# 07_GSM_EM05.net
KiCad netlist of a schematic drawn in Altium Designer
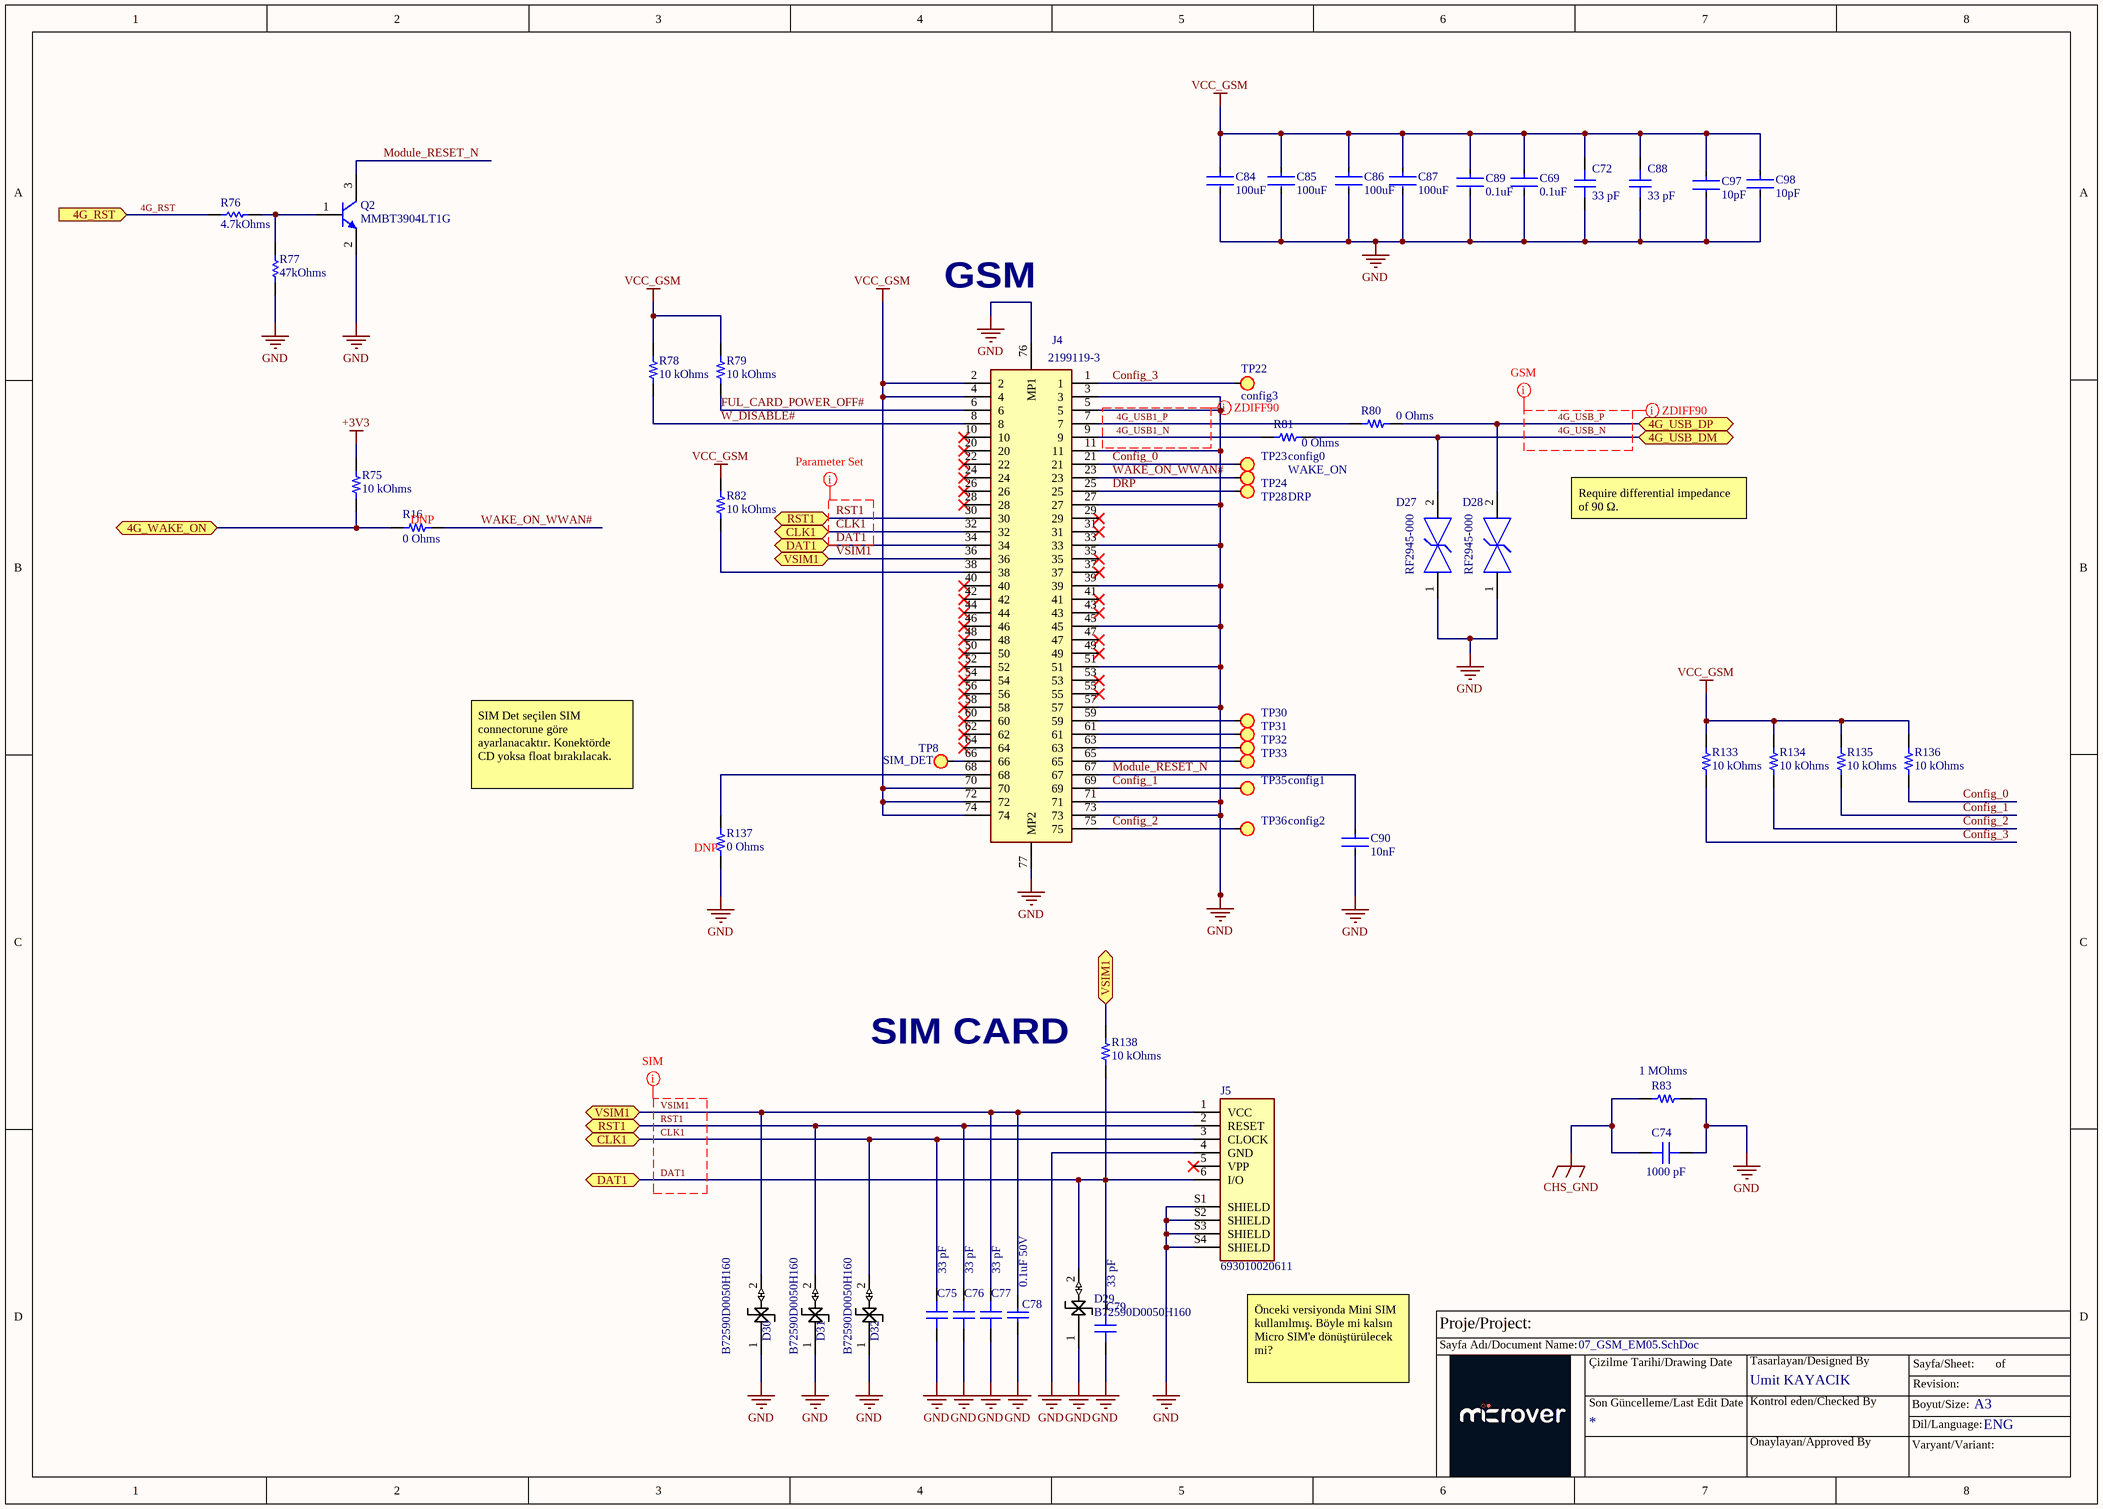
[diagram p0: 07_GSM_EM05.SchDoc]

(export (version "E")
  (design (tool "Eeschema 10.0.6"))
  (components
    (comp (ref "C69")
      (value "0.1uF")
      (footprint "FP-GRM15-MFG")
      (description "CAP CER 0.1UF 16V X7R 0402")
      (fields (field (name "PART NUMBER") "GRM155R71C104KA88D") (field (name "TOLERANCE") "10%"))
      (libsource (lib "Altium Content Vault") (part "236180d848d6139a670b325ea6854c9"))
    )
    (comp (ref "C72")
      (value "33 pF")
      (footprint "CAP0402(1005)X0.5")
      (description "CAP CER 33PF 25V C0G/NP0 0402")
      (fields (field (name "PART NUMBER") "885012005043") (field (name "MANUFACTURER") "Würth Elektronik"))
      (libsource (lib "Celestial Altium Library - altium_library") (part "Capacitor"))
    )
    (comp (ref "C74")
      (value "1000 pF")
      (footprint "CAP 1206_3216 - 0.8MM")
      (description "CAP CER 1000PF 2KV X7R 1206")
      (fields (field (name "PART NUMBER") "202R18W102KV4E"))
      (libsource (lib "Celestial Altium Library - altium_library") (part "Capacitor"))
    )
    (comp (ref "C75")
      (value "33 pF")
      (footprint "CAP 0402_1005")
      (description "CAP CER 33PF 25V C0G/NP0 0402")
      (fields (field (name "PART NUMBER") "885012005043") (field (name "MANUFACTURER") "Würth Elektronik"))
      (libsource (lib "Celestial Altium Library - altium_library") (part "Capacitor"))
    )
    (comp (ref "C76")
      (value "33 pF")
      (footprint "CAP 0402_1005")
      (description "CAP CER 33PF 25V C0G/NP0 0402")
      (fields (field (name "PART NUMBER") "885012005043") (field (name "MANUFACTURER") "Würth Elektronik"))
      (libsource (lib "Celestial Altium Library - altium_library") (part "Capacitor"))
    )
    (comp (ref "C77")
      (value "33 pF")
      (footprint "CAP 0402_1005")
      (description "CAP CER 33PF 25V C0G/NP0 0402")
      (fields (field (name "PART NUMBER") "885012005043") (field (name "MANUFACTURER") "Würth Elektronik"))
      (libsource (lib "Celestial Altium Library - altium_library") (part "Capacitor"))
    )
    (comp (ref "C78")
      (value "0.1uF 50V")
      (footprint "SMC0603")
      (description "0.1 µF ±10% 50V Ceramic Capacitor X7R 0603 (1608 Metric)")
      (fields
        (field (name "MANUFACTURER PART NUMBER") "CL10B104KB8NNNL")
        (field (name "LCSC PART NUMBER") "C1591")
      )
      (libsource (lib "HW_HOLLAND_NCDM_MONITOR_R1") (part "CAP0603_0.1UF_50V"))
    )
    (comp (ref "C79")
      (value "33 pF")
      (footprint "CAP 0402_1005")
      (description "CAP CER 33PF 25V C0G/NP0 0402")
      (fields (field (name "PART NUMBER") "885012005043") (field (name "MANUFACTURER") "Würth Elektronik"))
      (libsource (lib "Celestial Altium Library - altium_library") (part "Capacitor"))
    )
    (comp (ref "C84")
      (value "100uF")
      (footprint "FP-C3216-160-0_3-IPC_C")
      (description "Multilayer Ceramic Capacitors 100uF ±20% 10V X5R SMD 1206")
      (fields (field (name "VOLTAGE") "10V") (field (name "TOLERANCE") "20%"))
      (libsource (lib "Altium Content Vault") (part "02cd4be3c70576c341d710602a673aa"))
    )
    (comp (ref "C85")
      (value "100uF")
      (footprint "FP-C3216-160-0_3-IPC_C")
      (description "Multilayer Ceramic Capacitors 100uF ±20% 10V X5R SMD 1206")
      (fields (field (name "VOLTAGE") "10V") (field (name "TOLERANCE") "20%"))
      (libsource (lib "Altium Content Vault") (part "02cd4be3c70576c341d710602a673aa"))
    )
    (comp (ref "C86")
      (value "100uF")
      (footprint "FP-C3216-160-0_3-IPC_C")
      (description "Multilayer Ceramic Capacitors 100uF ±20% 10V X5R SMD 1206")
      (fields (field (name "VOLTAGE") "10V") (field (name "TOLERANCE") "20%"))
      (libsource (lib "Altium Content Vault") (part "02cd4be3c70576c341d710602a673aa"))
    )
    (comp (ref "C87")
      (value "100uF")
      (footprint "FP-C3216-160-0_3-IPC_C")
      (description "Multilayer Ceramic Capacitors 100uF ±20% 10V X5R SMD 1206")
      (fields (field (name "VOLTAGE") "10V") (field (name "TOLERANCE") "20%"))
      (libsource (lib "Altium Content Vault") (part "02cd4be3c70576c341d710602a673aa"))
    )
    (comp (ref "C88")
      (value "33 pF")
      (footprint "CAP0402(1005)X0.5")
      (description "CAP CER 33PF 25V C0G/NP0 0402")
      (fields (field (name "PART NUMBER") "885012005043") (field (name "MANUFACTURER") "Würth Elektronik"))
      (libsource (lib "Celestial Altium Library - altium_library") (part "Capacitor"))
    )
    (comp (ref "C89")
      (value "0.1uF")
      (footprint "FP-GRM15-MFG")
      (description "CAP CER 0.1UF 16V X7R 0402")
      (fields (field (name "PART NUMBER") "GRM155R71C104KA88D") (field (name "TOLERANCE") "10%"))
      (libsource (lib "Altium Content Vault") (part "236180d848d6139a670b325ea6854c9"))
    )
    (comp (ref "C90")
      (value "10nF")
      (footprint "FP-CL165-IPC_C")
      (description "Cap Ceramic 10nF 50V X7R ±10% SMD 0402 +125°C Paper T/R")
      (fields (field (name "VOLTAGE") "50V") (field (name "TOLERANCE") "10%"))
      (libsource (lib "Altium Content Vault") (part "b4654b650e69147ec39a6b967a45e02"))
    )
    (comp (ref "C97")
      (value "10pF")
      (footprint "FP-CGA2B-MFG")
      (description "Cap Ceramic 10pF 50V C0G 0.5pF Pad SMD 0402 +125°C Automotive T/R")
      (fields (field (name "PART NUMBER") "CGA2B2C0G1H100D050BA"))
      (libsource (lib "Altium Content Vault") (part "b4654b650e69147ec39a6b967a45e02"))
    )
    (comp (ref "C98")
      (value "10pF")
      (footprint "FP-CGA2B-MFG")
      (description "Cap Ceramic 10pF 50V C0G 0.5pF Pad SMD 0402 +125°C Automotive T/R")
      (fields (field (name "PART NUMBER") "CGA2B2C0G1H100D050BA"))
      (libsource (lib "Altium Content Vault") (part "b4654b650e69147ec39a6b967a45e02"))
    )
    (comp (ref "D27")
      (value "RF2945-000")
      (footprint "FP-SESD0402-MFG")
      (description "TVS DIODE 7V 10V 0402")
      (fields
        (field (name "OCTOPART") "https://octopart.com/rf2945-000-littelfuse-56516902")
        (field (name "MANUFACTURER") "Littelfuse")
      )
      (libsource (lib "Altium Content Vault") (part "876f4347bf90aa6f500f43e3cd03972"))
    )
    (comp (ref "D28")
      (value "RF2945-000")
      (footprint "FP-SESD0402-MFG")
      (description "TVS DIODE 7V 10V 0402")
      (fields
        (field (name "OCTOPART") "https://octopart.com/rf2945-000-littelfuse-56516902")
        (field (name "MANUFACTURER") "Littelfuse")
      )
      (libsource (lib "Altium Content Vault") (part "876f4347bf90aa6f500f43e3cd03972"))
    )
    (comp (ref "D29")
      (value "B72590D0050H160")
      (footprint "SOD1005X60N")
      (description "VARISTOR 150V 0402")
      (fields (field (name "MANUFACTURER") "TDK EPCOS"))
      (libsource (lib "HW_HOLLAND_NCDM_MONITOR_R1") (part "B72590D0050H160"))
    )
    (comp (ref "D30")
      (value "B72590D0050H160")
      (footprint "SOD1005X60N")
      (description "VARISTOR 150V 0402")
      (fields (field (name "MANUFACTURER") "TDK EPCOS"))
      (libsource (lib "HW_HOLLAND_NCDM_MONITOR_R1") (part "B72590D0050H160"))
    )
    (comp (ref "D31")
      (value "B72590D0050H160")
      (footprint "SOD1005X60N")
      (description "VARISTOR 150V 0402")
      (fields (field (name "MANUFACTURER") "TDK EPCOS"))
      (libsource (lib "HW_HOLLAND_NCDM_MONITOR_R1") (part "B72590D0050H160"))
    )
    (comp (ref "D32")
      (value "B72590D0050H160")
      (footprint "SOD1005X60N")
      (description "VARISTOR 150V 0402")
      (fields (field (name "MANUFACTURER") "TDK EPCOS"))
      (libsource (lib "HW_HOLLAND_NCDM_MONITOR_R1") (part "B72590D0050H160"))
    )
    (comp (ref "J4")
      (value "2199119-3")
      (footprint "2199119-3")
      (description "Conn Power Card Edge Socket 67 POS 0.5mm Solder RA SMD T/R")
      (fields (field (name "MANUFACTURER") "TE Connectivity"))
      (libsource (lib "HW_HOLLAND_NCDM_MONITOR_R1") (part "2199119-3"))
    )
    (comp (ref "J5")
      (value "693010020611")
      (footprint "WURTH_693010020611")
      (description "WR-CRD Mini SIM Card Connector Header Shielded")
      (fields (field (name "MANUFACTURER") "Wurth Electronics"))
      (libsource (lib "HW_HOLLAND_NCDM_MONITOR_R1") (part "693010020611"))
    )
    (comp (ref "Q2")
      (value "MMBT3904LT1G")
      (footprint "ONSC-SOT-23-3-318-08_V")
      (description "General Purpose Transistor, NPN Silicon, 3-Pin SOT-23, Pb-Free, Tape and Reel")
      (fields (field (name "MANUFACTURER") "On Semiconductor"))
      (libsource (lib "Altium Content Vault") (part "ONSC-NPN-B1E2C3-3"))
    )
    (comp (ref "R16")
      (value "0 Ohms")
      (footprint "RES0402(1005)")
      (description "RES 0 OHM JUMPER 1/8W 0402")
      (fields
        (field (name "PART NUMBER") "HCJ0402ZT0R00")
        (field (name "MANUFACTURER") "Stackpole Electronics Inc")
      )
      (libsource (lib "Celestial Altium Library - altium_library") (part "Resistor"))
    )
    (comp (ref "R75")
      (value "10 kOhms")
      (footprint "RES 0402_1005")
      (description "RES 10K OHM 0.1% 1/10W 0402")
      (fields
        (field (name "PART NUMBER") "RP73PF1E10KBTD")
        (field (name "MANUFACTURER") "TE Connectivity Passive Product")
      )
      (libsource (lib "Celestial Altium Library - altium_library") (part "Resistor"))
    )
    (comp (ref "R76")
      (value "4.7kOhms")
      (footprint "RESC1005X40X25NL05T10")
      (fields (field (name "MANUFACTURER") "Yageo / Phycomp") (field (name "PART NUMBER") "RC0402FR-074K7L"))
      (libsource (lib "Altium Content Vault") (part "RES"))
    )
    (comp (ref "R77")
      (value "47kOhms")
      (footprint "RESC1005X40X25ML05T10")
      (fields (field (name "PART NUMBER") "CRCW040247K0FKEDHP") (field (name "MANUFACTURER") "Vishay Dale"))
      (libsource (lib "Altium Content Vault") (part "RES"))
    )
    (comp (ref "R78")
      (value "10 kOhms")
      (footprint "RES 0402_1005")
      (description "RES 10K OHM 0.1% 1/10W 0402")
      (fields
        (field (name "PART NUMBER") "RP73PF1E10KBTD")
        (field (name "MANUFACTURER") "TE Connectivity Passive Product")
      )
      (libsource (lib "Celestial Altium Library - altium_library") (part "Resistor"))
    )
    (comp (ref "R79")
      (value "10 kOhms")
      (footprint "RES 0402_1005")
      (description "RES 10K OHM 0.1% 1/10W 0402")
      (fields
        (field (name "PART NUMBER") "RP73PF1E10KBTD")
        (field (name "MANUFACTURER") "TE Connectivity Passive Product")
      )
      (libsource (lib "Celestial Altium Library - altium_library") (part "Resistor"))
    )
    (comp (ref "R80")
      (value "0 Ohms")
      (footprint "RES 0402_1005")
      (description "RES 0 OHM JUMPER 1/8W 0402")
      (fields
        (field (name "PART NUMBER") "HCJ0402ZT0R00")
        (field (name "MANUFACTURER") "Stackpole Electronics Inc")
      )
      (libsource (lib "Celestial Altium Library - altium_library") (part "Resistor"))
    )
    (comp (ref "R81")
      (value "0 Ohms")
      (footprint "RES 0402_1005")
      (description "RES 0 OHM JUMPER 1/8W 0402")
      (fields
        (field (name "PART NUMBER") "HCJ0402ZT0R00")
        (field (name "MANUFACTURER") "Stackpole Electronics Inc")
      )
      (libsource (lib "Celestial Altium Library - altium_library") (part "Resistor"))
    )
    (comp (ref "R82")
      (value "10 kOhms")
      (footprint "RES 0402_1005")
      (description "RES 10K OHM 0.1% 1/10W 0402")
      (fields
        (field (name "PART NUMBER") "RP73PF1E10KBTD")
        (field (name "MANUFACTURER") "TE Connectivity Passive Product")
      )
      (libsource (lib "Celestial Altium Library - altium_library") (part "Resistor"))
    )
    (comp (ref "R83")
      (value "1 MOhms")
      (footprint "RES 0402_1005")
      (description "ANTI-SURGE CHIP RESISTORS")
      (fields (field (name "PART NUMBER") "ESR01MZPF1004"))
      (libsource (lib "Celestial Altium Library - altium_library") (part "Resistor"))
    )
    (comp (ref "R133")
      (value "10 kOhms")
      (footprint "RES0402(1005)")
      (description "RES 10K OHM 0.1% 1/10W 0402")
      (fields
        (field (name "PART NUMBER") "RP73PF1E10KBTD")
        (field (name "MANUFACTURER") "TE Connectivity Passive Product")
      )
      (libsource (lib "Celestial Altium Library - altium_library") (part "Resistor"))
    )
    (comp (ref "R134")
      (value "10 kOhms")
      (footprint "RES0402(1005)")
      (description "RES 10K OHM 0.1% 1/10W 0402")
      (fields
        (field (name "PART NUMBER") "RP73PF1E10KBTD")
        (field (name "MANUFACTURER") "TE Connectivity Passive Product")
      )
      (libsource (lib "Celestial Altium Library - altium_library") (part "Resistor"))
    )
    (comp (ref "R135")
      (value "10 kOhms")
      (footprint "RES0402(1005)")
      (description "RES 10K OHM 0.1% 1/10W 0402")
      (fields
        (field (name "PART NUMBER") "RP73PF1E10KBTD")
        (field (name "MANUFACTURER") "TE Connectivity Passive Product")
      )
      (libsource (lib "Celestial Altium Library - altium_library") (part "Resistor"))
    )
    (comp (ref "R136")
      (value "10 kOhms")
      (footprint "RES0402(1005)")
      (description "RES 10K OHM 0.1% 1/10W 0402")
      (fields
        (field (name "PART NUMBER") "RP73PF1E10KBTD")
        (field (name "MANUFACTURER") "TE Connectivity Passive Product")
      )
      (libsource (lib "Celestial Altium Library - altium_library") (part "Resistor"))
    )
    (comp (ref "R137")
      (value "0 Ohms")
      (footprint "RES0402(1005)")
      (description "RES 0 OHM JUMPER 1/8W 0402")
      (fields
        (field (name "PART NUMBER") "HCJ0402ZT0R00")
        (field (name "MANUFACTURER") "Stackpole Electronics Inc")
      )
      (libsource (lib "Celestial Altium Library - altium_library") (part "Resistor"))
    )
    (comp (ref "R138")
      (value "10 kOhms")
      (footprint "RES0402(1005)")
      (description "RES 10K OHM 0.1% 1/10W 0402")
      (fields
        (field (name "PART NUMBER") "RP73PF1E10KBTD")
        (field (name "MANUFACTURER") "TE Connectivity Passive Product")
      )
      (libsource (lib "Celestial Altium Library - altium_library") (part "Resistor"))
    )
    (comp (ref "TP8")
      (value "SIM_DET")
      (footprint "TEST_POINT")
      (libsource (lib "HW_HOLLAND_NCDM_MONITOR_R1") (part "TP_1"))
    )
    (comp (ref "TP22")
      (value "config3")
      (footprint "TEST_POINT")
      (libsource (lib "HW_HOLLAND_NCDM_MONITOR_R1") (part "TP_1"))
    )
    (comp (ref "TP23")
      (value "config0")
      (footprint "TEST_POINT")
      (libsource (lib "HW_HOLLAND_NCDM_MONITOR_R1") (part "TP_1"))
    )
    (comp (ref "TP24")
      (value "WAKE_ON")
      (footprint "TEST_POINT")
      (libsource (lib "HW_HOLLAND_NCDM_MONITOR_R1") (part "TP_1"))
    )
    (comp (ref "TP28")
      (value "DRP")
      (footprint "TEST_POINT")
      (libsource (lib "HW_HOLLAND_NCDM_MONITOR_R1") (part "TP_1"))
    )
    (comp (ref "TP30")
      (value "~")
      (footprint "TEST_POINT")
      (libsource (lib "HW_HOLLAND_NCDM_MONITOR_R1") (part "TP_1"))
    )
    (comp (ref "TP31")
      (value "config0")
      (footprint "TEST_POINT")
      (libsource (lib "HW_HOLLAND_NCDM_MONITOR_R1") (part "TP_1"))
    )
    (comp (ref "TP32")
      (value "~")
      (footprint "TEST_POINT")
      (libsource (lib "HW_HOLLAND_NCDM_MONITOR_R1") (part "TP_1"))
    )
    (comp (ref "TP33")
      (value "~")
      (footprint "TEST_POINT")
      (libsource (lib "HW_HOLLAND_NCDM_MONITOR_R1") (part "TP_1"))
    )
    (comp (ref "TP35")
      (value "config1")
      (footprint "TEST_POINT")
      (libsource (lib "HW_HOLLAND_NCDM_MONITOR_R1") (part "TP_1"))
    )
    (comp (ref "TP36")
      (value "config2")
      (footprint "TEST_POINT")
      (libsource (lib "HW_HOLLAND_NCDM_MONITOR_R1") (part "TP_1"))
    )
  )
  (nets
    (net (code "1") (name "+3V3") (class "Default")
      (node (ref "R75") (pin "2") (pinfunction "2_2") (pintype "passive"))
    )
    (net (code "2") (name "/4G_RST") (class "Default")
      (node (ref "R76") (pin "1") (pinfunction "1_1") (pintype "passive"))
    )
    (net (code "3") (name "/4G_USB1_N") (class "Default")
      (node (ref "J4") (pin "9") (pinfunction "9_9") (pintype "passive"))
      (node (ref "R81") (pin "2") (pinfunction "2_2") (pintype "passive"))
    )
    (net (code "4") (name "/4G_USB1_P") (class "Default")
      (node (ref "J4") (pin "7") (pinfunction "7_7") (pintype "passive"))
      (node (ref "R80") (pin "2") (pinfunction "2_2") (pintype "passive"))
    )
    (net (code "5") (name "/4G_USB_N") (class "Default")
      (node (ref "D27") (pin "2") (pinfunction "2_2") (pintype "passive"))
      (node (ref "R81") (pin "1") (pinfunction "1_1") (pintype "passive"))
    )
    (net (code "6") (name "/4G_USB_P") (class "Default")
      (node (ref "D28") (pin "2") (pinfunction "2_2") (pintype "passive"))
      (node (ref "R80") (pin "1") (pinfunction "1_1") (pintype "passive"))
    )
    (net (code "7") (name "/4G_WAKE_ON") (class "Default")
      (node (ref "R16") (pin "1") (pinfunction "1_1") (pintype "passive"))
      (node (ref "R75") (pin "1") (pinfunction "1_1") (pintype "passive"))
    )
    (net (code "8") (name "/CLK1") (class "Default")
      (node (ref "C75") (pin "2") (pinfunction "2_2") (pintype "passive"))
      (node (ref "D32") (pin "2") (pinfunction "I/OLINE_2") (pintype "bidirectional"))
      (node (ref "J4") (pin "32") (pinfunction "32_32") (pintype "passive"))
      (node (ref "J5") (pin "3") (pinfunction "CLOCK_3") (pintype "passive"))
    )
    (net (code "9") (name "/Config_0") (class "Default")
      (node (ref "J4") (pin "21") (pinfunction "21_21") (pintype "passive"))
      (node (ref "R136") (pin "1") (pinfunction "1_1") (pintype "passive"))
      (node (ref "TP23") (pin "1") (pinfunction "TP_1") (pintype "passive"))
    )
    (net (code "10") (name "/Config_1") (class "Default")
      (node (ref "J4") (pin "69") (pinfunction "69_69") (pintype "passive"))
      (node (ref "R135") (pin "1") (pinfunction "1_1") (pintype "passive"))
      (node (ref "TP35") (pin "1") (pinfunction "TP_1") (pintype "passive"))
    )
    (net (code "11") (name "/Config_2") (class "Default")
      (node (ref "J4") (pin "75") (pinfunction "75_75") (pintype "passive"))
      (node (ref "R134") (pin "1") (pinfunction "1_1") (pintype "passive"))
      (node (ref "TP36") (pin "1") (pinfunction "TP_1") (pintype "passive"))
    )
    (net (code "12") (name "/Config_3") (class "Default")
      (node (ref "J4") (pin "1") (pinfunction "1_1") (pintype "passive"))
      (node (ref "R133") (pin "1") (pinfunction "1_1") (pintype "passive"))
      (node (ref "TP22") (pin "1") (pinfunction "TP_1") (pintype "passive"))
    )
    (net (code "13") (name "/DAT1") (class "Default")
      (node (ref "C79") (pin "2") (pinfunction "2_2") (pintype "passive"))
      (node (ref "D29") (pin "2") (pinfunction "I/OLINE_2") (pintype "bidirectional"))
      (node (ref "J4") (pin "34") (pinfunction "34_34") (pintype "passive"))
      (node (ref "J5") (pin "6") (pinfunction "I/O_6") (pintype "passive"))
      (node (ref "R138") (pin "1") (pinfunction "1_1") (pintype "passive"))
    )
    (net (code "14") (name "/DRP") (class "Default")
      (node (ref "J4") (pin "25") (pinfunction "25_25") (pintype "passive"))
      (node (ref "TP28") (pin "1") (pinfunction "TP_1") (pintype "passive"))
    )
    (net (code "15") (name "/FUL_CARD_POWER_OFF#") (class "Default")
      (node (ref "J4") (pin "6") (pinfunction "6_6") (pintype "passive"))
      (node (ref "R79") (pin "1") (pinfunction "1_1") (pintype "passive"))
    )
    (net (code "16") (name "/Module_RESET_N") (class "Default")
      (node (ref "C90") (pin "1") (pinfunction "1_1") (pintype "passive"))
      (node (ref "J4") (pin "67") (pinfunction "67_67") (pintype "passive"))
      (node (ref "Q2") (pin "3") (pinfunction "C_3") (pintype "passive"))
    )
    (net (code "17") (name "/RST1") (class "Default")
      (node (ref "C76") (pin "2") (pinfunction "2_2") (pintype "passive"))
      (node (ref "D31") (pin "2") (pinfunction "I/OLINE_2") (pintype "bidirectional"))
      (node (ref "J4") (pin "30") (pinfunction "30_30") (pintype "passive"))
      (node (ref "J5") (pin "2") (pinfunction "RESET_2") (pintype "passive"))
    )
    (net (code "18") (name "/VSIM1") (class "Default")
      (node (ref "C77") (pin "2") (pinfunction "2_2") (pintype "passive"))
      (node (ref "C78") (pin "2") (pinfunction "2_2") (pintype "passive"))
      (node (ref "D30") (pin "2") (pinfunction "I/OLINE_2") (pintype "bidirectional"))
      (node (ref "J4") (pin "36") (pinfunction "36_36") (pintype "passive"))
      (node (ref "J5") (pin "1") (pinfunction "VCC_1") (pintype "passive"))
      (node (ref "R138") (pin "2") (pinfunction "2_2") (pintype "passive"))
    )
    (net (code "19") (name "/WAKE_ON_WWAN#") (class "Default")
      (node (ref "J4") (pin "23") (pinfunction "23_23") (pintype "passive"))
      (node (ref "R16") (pin "2") (pinfunction "2_2") (pintype "passive"))
      (node (ref "TP24") (pin "1") (pinfunction "TP_1") (pintype "passive"))
    )
    (net (code "20") (name "/W_DISABLE#") (class "Default")
      (node (ref "J4") (pin "8") (pinfunction "8_8") (pintype "passive"))
      (node (ref "R78") (pin "1") (pinfunction "1_1") (pintype "passive"))
    )
    (net (code "21") (name "CHS_GND") (class "Default")
      (node (ref "C74") (pin "1") (pinfunction "1_1") (pintype "passive"))
      (node (ref "R83") (pin "1") (pinfunction "1_1") (pintype "passive"))
    )
    (net (code "22") (name "GND") (class "Default")
      (node (ref "C69") (pin "1") (pinfunction "1_1") (pintype "passive"))
      (node (ref "C72") (pin "1") (pinfunction "1_1") (pintype "passive"))
      (node (ref "C74") (pin "2") (pinfunction "2_2") (pintype "passive"))
      (node (ref "C75") (pin "1") (pinfunction "1_1") (pintype "passive"))
      (node (ref "C76") (pin "1") (pinfunction "1_1") (pintype "passive"))
      (node (ref "C77") (pin "1") (pinfunction "1_1") (pintype "passive"))
      (node (ref "C78") (pin "1") (pinfunction "1_1") (pintype "passive"))
      (node (ref "C79") (pin "1") (pinfunction "1_1") (pintype "passive"))
      (node (ref "C84") (pin "2") (pinfunction "2_2") (pintype "passive"))
      (node (ref "C85") (pin "2") (pinfunction "2_2") (pintype "passive"))
      (node (ref "C86") (pin "2") (pinfunction "2_2") (pintype "passive"))
      (node (ref "C87") (pin "2") (pinfunction "2_2") (pintype "passive"))
      (node (ref "C88") (pin "1") (pinfunction "1_1") (pintype "passive"))
      (node (ref "C89") (pin "1") (pinfunction "1_1") (pintype "passive"))
      (node (ref "C90") (pin "2") (pinfunction "2_2") (pintype "passive"))
      (node (ref "C97") (pin "2") (pinfunction "2_2") (pintype "passive"))
      (node (ref "C98") (pin "2") (pinfunction "2_2") (pintype "passive"))
      (node (ref "D27") (pin "1") (pinfunction "1_1") (pintype "passive"))
      (node (ref "D28") (pin "1") (pinfunction "1_1") (pintype "passive"))
      (node (ref "D29") (pin "1") (pinfunction "GND_1") (pintype "passive"))
      (node (ref "D30") (pin "1") (pinfunction "GND_1") (pintype "passive"))
      (node (ref "D31") (pin "1") (pinfunction "GND_1") (pintype "passive"))
      (node (ref "D32") (pin "1") (pinfunction "GND_1") (pintype "passive"))
      (node (ref "J4") (pin "11") (pinfunction "11_11") (pintype "passive"))
      (node (ref "J4") (pin "27") (pinfunction "27_27") (pintype "passive"))
      (node (ref "J4") (pin "3") (pinfunction "3_3") (pintype "passive"))
      (node (ref "J4") (pin "33") (pinfunction "33_33") (pintype "passive"))
      (node (ref "J4") (pin "39") (pinfunction "39_39") (pintype "passive"))
      (node (ref "J4") (pin "45") (pinfunction "45_45") (pintype "passive"))
      (node (ref "J4") (pin "5") (pinfunction "5_5") (pintype "passive"))
      (node (ref "J4") (pin "51") (pinfunction "51_51") (pintype "passive"))
      (node (ref "J4") (pin "57") (pinfunction "57_57") (pintype "passive"))
      (node (ref "J4") (pin "71") (pinfunction "71_71") (pintype "passive"))
      (node (ref "J4") (pin "73") (pinfunction "73_73") (pintype "passive"))
      (node (ref "J4") (pin "76") (pinfunction "MP1_76") (pintype "passive"))
      (node (ref "J4") (pin "77") (pinfunction "MP2_77") (pintype "passive"))
      (node (ref "J5") (pin "4") (pinfunction "GND_4") (pintype "passive"))
      (node (ref "J5") (pin "S1") (pinfunction "SHIELD_S1") (pintype "passive"))
      (node (ref "J5") (pin "S2") (pinfunction "SHIELD_S2") (pintype "passive"))
      (node (ref "J5") (pin "S3") (pinfunction "SHIELD_S3") (pintype "passive"))
      (node (ref "J5") (pin "S4") (pinfunction "SHIELD_S4") (pintype "passive"))
      (node (ref "Q2") (pin "2") (pinfunction "E_2") (pintype "passive"))
      (node (ref "R137") (pin "2") (pinfunction "2_2") (pintype "passive"))
      (node (ref "R77") (pin "1") (pinfunction "1_1") (pintype "passive"))
      (node (ref "R83") (pin "2") (pinfunction "2_2") (pintype "passive"))
    )
    (net (code "23") (name "Net-(J4-Pad38)") (class "Default")
      (node (ref "J4") (pin "38") (pinfunction "38_38") (pintype "passive"))
      (node (ref "R82") (pin "1") (pinfunction "1_1") (pintype "passive"))
    )
    (net (code "24") (name "Net-(J4-Pad68)") (class "Default")
      (node (ref "J4") (pin "68") (pinfunction "68_68") (pintype "passive"))
      (node (ref "R137") (pin "1") (pinfunction "1_1") (pintype "passive"))
    )
    (net (code "25") (name "Net-(Q2-B)") (class "Default")
      (node (ref "Q2") (pin "1") (pinfunction "B_1") (pintype "passive"))
      (node (ref "R76") (pin "2") (pinfunction "2_2") (pintype "passive"))
      (node (ref "R77") (pin "2") (pinfunction "2_2") (pintype "passive"))
    )
    (net (code "26") (name "Net-(TP8-TP)") (class "Default")
      (node (ref "J4") (pin "66") (pinfunction "66_66") (pintype "passive"))
      (node (ref "TP8") (pin "1") (pinfunction "TP_1") (pintype "passive"))
    )
    (net (code "27") (name "Net-(TP30-TP)") (class "Default")
      (node (ref "J4") (pin "59") (pinfunction "59_59") (pintype "passive"))
      (node (ref "TP30") (pin "1") (pinfunction "TP_1") (pintype "passive"))
    )
    (net (code "28") (name "Net-(TP31-TP)") (class "Default")
      (node (ref "J4") (pin "61") (pinfunction "61_61") (pintype "passive"))
      (node (ref "TP31") (pin "1") (pinfunction "TP_1") (pintype "passive"))
    )
    (net (code "29") (name "Net-(TP32-TP)") (class "Default")
      (node (ref "J4") (pin "63") (pinfunction "63_63") (pintype "passive"))
      (node (ref "TP32") (pin "1") (pinfunction "TP_1") (pintype "passive"))
    )
    (net (code "30") (name "Net-(TP33-TP)") (class "Default")
      (node (ref "J4") (pin "65") (pinfunction "65_65") (pintype "passive"))
      (node (ref "TP33") (pin "1") (pinfunction "TP_1") (pintype "passive"))
    )
    (net (code "31") (name "VCC_GSM") (class "Default")
      (node (ref "C69") (pin "2") (pinfunction "2_2") (pintype "passive"))
      (node (ref "C72") (pin "2") (pinfunction "2_2") (pintype "passive"))
      (node (ref "C84") (pin "1") (pinfunction "1_1") (pintype "passive"))
      (node (ref "C85") (pin "1") (pinfunction "1_1") (pintype "passive"))
      (node (ref "C86") (pin "1") (pinfunction "1_1") (pintype "passive"))
      (node (ref "C87") (pin "1") (pinfunction "1_1") (pintype "passive"))
      (node (ref "C88") (pin "2") (pinfunction "2_2") (pintype "passive"))
      (node (ref "C89") (pin "2") (pinfunction "2_2") (pintype "passive"))
      (node (ref "C97") (pin "1") (pinfunction "1_1") (pintype "passive"))
      (node (ref "C98") (pin "1") (pinfunction "1_1") (pintype "passive"))
      (node (ref "J4") (pin "2") (pinfunction "2_2") (pintype "passive"))
      (node (ref "J4") (pin "4") (pinfunction "4_4") (pintype "passive"))
      (node (ref "J4") (pin "70") (pinfunction "70_70") (pintype "passive"))
      (node (ref "J4") (pin "72") (pinfunction "72_72") (pintype "passive"))
      (node (ref "J4") (pin "74") (pinfunction "74_74") (pintype "passive"))
      (node (ref "R133") (pin "2") (pinfunction "2_2") (pintype "passive"))
      (node (ref "R134") (pin "2") (pinfunction "2_2") (pintype "passive"))
      (node (ref "R135") (pin "2") (pinfunction "2_2") (pintype "passive"))
      (node (ref "R136") (pin "2") (pinfunction "2_2") (pintype "passive"))
      (node (ref "R78") (pin "2") (pinfunction "2_2") (pintype "passive"))
      (node (ref "R79") (pin "2") (pinfunction "2_2") (pintype "passive"))
      (node (ref "R82") (pin "2") (pinfunction "2_2") (pintype "passive"))
    )
    (net (code "32") (name "unconnected-(J4-Pad10)") (class "Default")
      (node (ref "J4") (pin "10") (pinfunction "10_10") (pintype "passive+no_connect"))
    )
    (net (code "33") (name "unconnected-(J4-Pad20)") (class "Default")
      (node (ref "J4") (pin "20") (pinfunction "20_20") (pintype "passive+no_connect"))
    )
    (net (code "34") (name "unconnected-(J4-Pad22)") (class "Default")
      (node (ref "J4") (pin "22") (pinfunction "22_22") (pintype "passive+no_connect"))
    )
    (net (code "35") (name "unconnected-(J4-Pad24)") (class "Default")
      (node (ref "J4") (pin "24") (pinfunction "24_24") (pintype "passive+no_connect"))
    )
    (net (code "36") (name "unconnected-(J4-Pad26)") (class "Default")
      (node (ref "J4") (pin "26") (pinfunction "26_26") (pintype "passive+no_connect"))
    )
    (net (code "37") (name "unconnected-(J4-Pad28)") (class "Default")
      (node (ref "J4") (pin "28") (pinfunction "28_28") (pintype "passive+no_connect"))
    )
    (net (code "38") (name "unconnected-(J4-Pad29)") (class "Default")
      (node (ref "J4") (pin "29") (pinfunction "29_29") (pintype "passive+no_connect"))
    )
    (net (code "39") (name "unconnected-(J4-Pad31)") (class "Default")
      (node (ref "J4") (pin "31") (pinfunction "31_31") (pintype "passive+no_connect"))
    )
    (net (code "40") (name "unconnected-(J4-Pad35)") (class "Default")
      (node (ref "J4") (pin "35") (pinfunction "35_35") (pintype "passive+no_connect"))
    )
    (net (code "41") (name "unconnected-(J4-Pad37)") (class "Default")
      (node (ref "J4") (pin "37") (pinfunction "37_37") (pintype "passive+no_connect"))
    )
    (net (code "42") (name "unconnected-(J4-Pad40)") (class "Default")
      (node (ref "J4") (pin "40") (pinfunction "40_40") (pintype "passive+no_connect"))
    )
    (net (code "43") (name "unconnected-(J4-Pad41)") (class "Default")
      (node (ref "J4") (pin "41") (pinfunction "41_41") (pintype "passive+no_connect"))
    )
    (net (code "44") (name "unconnected-(J4-Pad42)") (class "Default")
      (node (ref "J4") (pin "42") (pinfunction "42_42") (pintype "passive+no_connect"))
    )
    (net (code "45") (name "unconnected-(J4-Pad43)") (class "Default")
      (node (ref "J4") (pin "43") (pinfunction "43_43") (pintype "passive+no_connect"))
    )
    (net (code "46") (name "unconnected-(J4-Pad44)") (class "Default")
      (node (ref "J4") (pin "44") (pinfunction "44_44") (pintype "passive+no_connect"))
    )
    (net (code "47") (name "unconnected-(J4-Pad46)") (class "Default")
      (node (ref "J4") (pin "46") (pinfunction "46_46") (pintype "passive+no_connect"))
    )
    (net (code "48") (name "unconnected-(J4-Pad47)") (class "Default")
      (node (ref "J4") (pin "47") (pinfunction "47_47") (pintype "passive+no_connect"))
    )
    (net (code "49") (name "unconnected-(J4-Pad48)") (class "Default")
      (node (ref "J4") (pin "48") (pinfunction "48_48") (pintype "passive+no_connect"))
    )
    (net (code "50") (name "unconnected-(J4-Pad49)") (class "Default")
      (node (ref "J4") (pin "49") (pinfunction "49_49") (pintype "passive+no_connect"))
    )
    (net (code "51") (name "unconnected-(J4-Pad50)") (class "Default")
      (node (ref "J4") (pin "50") (pinfunction "50_50") (pintype "passive+no_connect"))
    )
    (net (code "52") (name "unconnected-(J4-Pad52)") (class "Default")
      (node (ref "J4") (pin "52") (pinfunction "52_52") (pintype "passive+no_connect"))
    )
    (net (code "53") (name "unconnected-(J4-Pad53)") (class "Default")
      (node (ref "J4") (pin "53") (pinfunction "53_53") (pintype "passive+no_connect"))
    )
    (net (code "54") (name "unconnected-(J4-Pad54)") (class "Default")
      (node (ref "J4") (pin "54") (pinfunction "54_54") (pintype "passive+no_connect"))
    )
    (net (code "55") (name "unconnected-(J4-Pad55)") (class "Default")
      (node (ref "J4") (pin "55") (pinfunction "55_55") (pintype "passive+no_connect"))
    )
    (net (code "56") (name "unconnected-(J4-Pad56)") (class "Default")
      (node (ref "J4") (pin "56") (pinfunction "56_56") (pintype "passive+no_connect"))
    )
    (net (code "57") (name "unconnected-(J4-Pad58)") (class "Default")
      (node (ref "J4") (pin "58") (pinfunction "58_58") (pintype "passive+no_connect"))
    )
    (net (code "58") (name "unconnected-(J4-Pad60)") (class "Default")
      (node (ref "J4") (pin "60") (pinfunction "60_60") (pintype "passive+no_connect"))
    )
    (net (code "59") (name "unconnected-(J4-Pad62)") (class "Default")
      (node (ref "J4") (pin "62") (pinfunction "62_62") (pintype "passive+no_connect"))
    )
    (net (code "60") (name "unconnected-(J4-Pad64)") (class "Default")
      (node (ref "J4") (pin "64") (pinfunction "64_64") (pintype "passive+no_connect"))
    )
    (net (code "61") (name "unconnected-(J5-VPP-Pad5)") (class "Default")
      (node (ref "J5") (pin "5") (pinfunction "VPP_5") (pintype "passive+no_connect"))
    )
  )
)
